# Candunio.net
KiCad netlist of a schematic drawn in Altium Designer
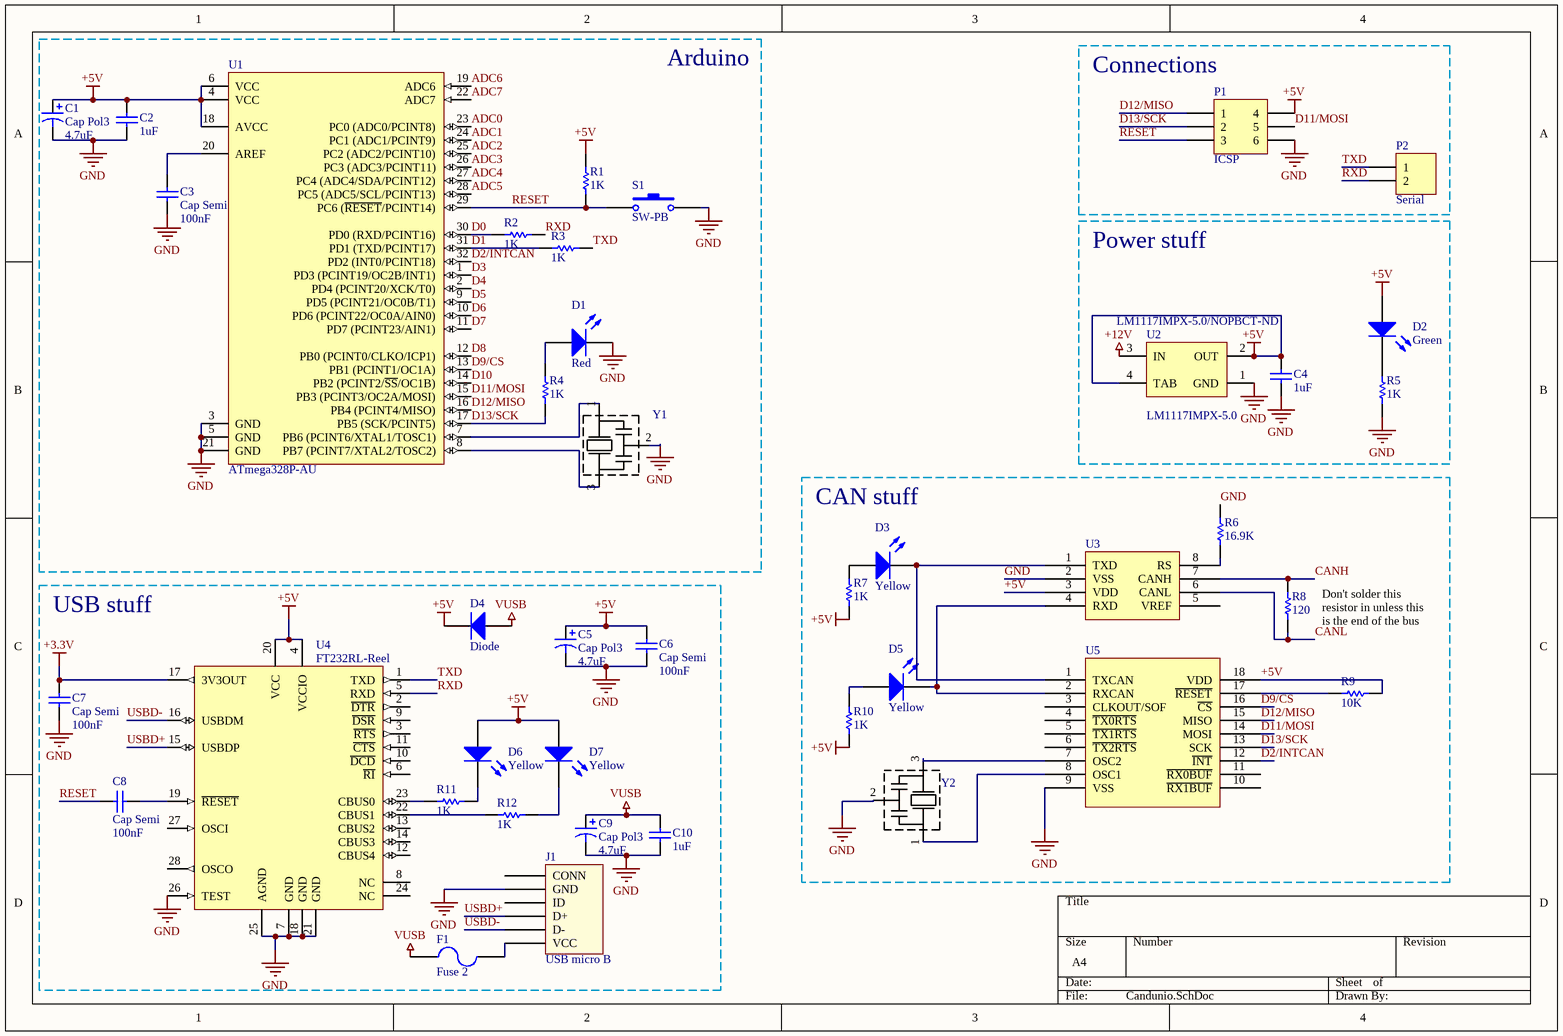
[diagram p0: Candunio.SchDoc]

(export (version "E")
  (design (tool "Eeschema 10.0.6"))
  (components
    (comp (ref "C1")
      (value "Cap Pol3")
      (footprint "C1206")
      (description "Polarized Capacitor (Surface Mount)")
      (fields
        (field (name "ALTIUM_VALUE") "4.7uF")
        (field (name "MANUFACTURER") "Kyocera AVX")
        (field (name "MANUFACTURER PART NUMBER") "12063C475KAT2A")
        (field (name "PUBLISHER") "Altium Limited")
      )
      (libsource (lib "Miscellaneous Devices") (part "Cap Pol3"))
    )
    (comp (ref "C2")
      (value "1uF")
      (footprint "C1206")
      (description "Capacitor (Semiconductor SIM Model)")
      (fields
        (field (name "MANUFACTURER") "Murata")
        (field (name "MANUFACTURER PART NUMBER") "GRM31MR71H105KA88L")
        (field (name "PUBLISHER") "Altium Limited")
      )
      (libsource (lib "Miscellaneous Devices") (part "Cap Semi"))
    )
    (comp (ref "C3")
      (value "Cap Semi")
      (footprint "C1206")
      (description "Capacitor (Semiconductor SIM Model)")
      (fields
        (field (name "ALTIUM_VALUE") "100nF")
        (field (name "MANUFACTURER") "Yageo")
        (field (name "MANUFACTURER PART NUMBER") "CC1206KKX7R0BB104")
        (field (name "PUBLISHER") "Altium Limited")
      )
      (libsource (lib "Miscellaneous Devices") (part "Cap Semi"))
    )
    (comp (ref "C4")
      (value "1uF")
      (footprint "C1206")
      (description "Capacitor (Semiconductor SIM Model)")
      (fields
        (field (name "MANUFACTURER") "Murata")
        (field (name "MANUFACTURER PART NUMBER") "GRM31MR71H105KA88L")
        (field (name "PUBLISHER") "Altium Limited")
      )
      (libsource (lib "Miscellaneous Devices") (part "Cap Semi"))
    )
    (comp (ref "C5")
      (value "Cap Pol3")
      (footprint "C1206")
      (description "Polarized Capacitor (Surface Mount)")
      (fields
        (field (name "ALTIUM_VALUE") "4.7uF")
        (field (name "MANUFACTURER") "Kyocera AVX")
        (field (name "MANUFACTURER PART NUMBER") "12063C475KAT2A")
        (field (name "PUBLISHER") "Altium Limited")
      )
      (libsource (lib "Miscellaneous Devices") (part "Cap Pol3"))
    )
    (comp (ref "C6")
      (value "Cap Semi")
      (footprint "C1206")
      (description "Capacitor (Semiconductor SIM Model)")
      (fields
        (field (name "ALTIUM_VALUE") "100nF")
        (field (name "MANUFACTURER") "Yageo")
        (field (name "MANUFACTURER PART NUMBER") "CC1206KKX7R0BB104")
        (field (name "PUBLISHER") "Altium Limited")
      )
      (libsource (lib "Miscellaneous Devices") (part "Cap Semi"))
    )
    (comp (ref "C7")
      (value "Cap Semi")
      (footprint "C1206")
      (description "Capacitor (Semiconductor SIM Model)")
      (fields
        (field (name "ALTIUM_VALUE") "100nF")
        (field (name "MANUFACTURER") "Yageo")
        (field (name "MANUFACTURER PART NUMBER") "CC1206KKX7R0BB104")
        (field (name "PUBLISHER") "Altium Limited")
      )
      (libsource (lib "Miscellaneous Devices") (part "Cap Semi"))
    )
    (comp (ref "C8")
      (value "Cap Semi")
      (footprint "C1206")
      (description "Capacitor (Semiconductor SIM Model)")
      (fields
        (field (name "ALTIUM_VALUE") "100nF")
        (field (name "MANUFACTURER") "Yageo")
        (field (name "MANUFACTURER PART NUMBER") "CC1206KKX7R0BB104")
        (field (name "PUBLISHER") "Altium Limited")
      )
      (libsource (lib "Miscellaneous Devices") (part "Cap Semi"))
    )
    (comp (ref "C9")
      (value "Cap Pol3")
      (footprint "C1206")
      (description "Polarized Capacitor (Surface Mount)")
      (fields
        (field (name "ALTIUM_VALUE") "4.7uF")
        (field (name "MANUFACTURER") "Kyocera AVX")
        (field (name "MANUFACTURER PART NUMBER") "12063C475KAT2A")
        (field (name "PUBLISHER") "Altium Limited")
      )
      (libsource (lib "Miscellaneous Devices") (part "Cap Pol3"))
    )
    (comp (ref "C10")
      (value "1uF")
      (footprint "C1206")
      (description "Capacitor (Semiconductor SIM Model)")
      (fields
        (field (name "MANUFACTURER") "Murata")
        (field (name "MANUFACTURER PART NUMBER") "GRM31MR71H105KA88L")
        (field (name "PUBLISHER") "Altium Limited")
      )
      (libsource (lib "Miscellaneous Devices") (part "Cap Semi"))
    )
    (comp (ref "D1")
      (value "Red")
      (footprint "3.2X1.6X1.1")
      (description "Typical RED, GREEN, YELLOW, AMBER GaAs LED")
      (fields
        (field (name "MANUFACTURER") "Broadcom Avago")
        (field (name "MANUFACTURER PART NUMBER") "HSMY-C150")
        (field (name "PUBLISHER") "Altium Limited")
      )
      (libsource (lib "Miscellaneous Devices") (part "LED2"))
    )
    (comp (ref "D2")
      (value "Green")
      (footprint "3.2X1.6X1.1")
      (description "Typical RED, GREEN, YELLOW, AMBER GaAs LED")
      (fields
        (field (name "MANUFACTURER") "Broadcom Avago")
        (field (name "MANUFACTURER PART NUMBER") "HSMG-C150")
        (field (name "PUBLISHER") "Altium Limited")
      )
      (libsource (lib "Miscellaneous Devices") (part "LED2"))
    )
    (comp (ref "D3")
      (value "Yellow")
      (footprint "3.2X1.6X1.1")
      (description "Typical RED, GREEN, YELLOW, AMBER GaAs LED")
      (fields
        (field (name "MANUFACTURER") "Broadcom Avago")
        (field (name "MANUFACTURER PART NUMBER") "HSMY-C150")
        (field (name "PUBLISHER") "Altium Limited")
      )
      (libsource (lib "Miscellaneous Devices") (part "LED2"))
    )
    (comp (ref "D4")
      (value "Diode")
      (footprint "SMC")
      (description "Default Diode")
      (fields (field (name "PUBLISHER") "Altium Limited"))
      (libsource (lib "Miscellaneous Devices") (part "Diode"))
    )
    (comp (ref "D5")
      (value "Yellow")
      (footprint "3.2X1.6X1.1")
      (description "Typical RED, GREEN, YELLOW, AMBER GaAs LED")
      (fields
        (field (name "MANUFACTURER") "Broadcom Avago")
        (field (name "MANUFACTURER PART NUMBER") "HSMY-C150")
        (field (name "PUBLISHER") "Altium Limited")
      )
      (libsource (lib "Miscellaneous Devices") (part "LED2"))
    )
    (comp (ref "D6")
      (value "Yellow")
      (footprint "3.2X1.6X1.1")
      (description "Typical RED, GREEN, YELLOW, AMBER GaAs LED")
      (fields
        (field (name "MANUFACTURER") "Broadcom Avago")
        (field (name "MANUFACTURER PART NUMBER") "HSMY-C150")
        (field (name "PUBLISHER") "Altium Limited")
      )
      (libsource (lib "Miscellaneous Devices") (part "LED2"))
    )
    (comp (ref "D7")
      (value "Yellow")
      (footprint "3.2X1.6X1.1")
      (description "Typical RED, GREEN, YELLOW, AMBER GaAs LED")
      (fields
        (field (name "MANUFACTURER") "Broadcom Avago")
        (field (name "MANUFACTURER PART NUMBER") "HSMY-C150")
        (field (name "PUBLISHER") "Altium Limited")
      )
      (libsource (lib "Miscellaneous Devices") (part "LED2"))
    )
    (comp (ref "F1")
      (value "Fuse 2")
      (footprint "1812")
      (description "Fuse")
      (fields
        (field (name "PART NUMBER") "MF-MSMF050-2")
        (field (name "MANUFACTURER") "Bourns")
        (field (name "PUBLISHER") "Altium Limited")
      )
      (libsource (lib "Miscellaneous Devices") (part "Fuse 2"))
    )
    (comp (ref "J1")
      (value "USB micro B")
      (footprint "1050170001")
      (description "CONN SM TH USB MICRO MODIFIED FOR DRILL")
      (fields (field (name "PART NUMBER") "WM1399CT-ND"))
      (libsource (lib "electronpowered") (part "1050170001"))
    )
    (comp (ref "P1")
      (value "ICSP")
      (footprint "HDR2X3_CEN")
      (description "Header, 3-Pin, Dual row")
      (fields (field (name "PUBLISHER") "Altium Limited"))
      (libsource (lib "Miscellaneous Connectors") (part "Header 3X2A"))
    )
    (comp (ref "P2")
      (value "Serial")
      (footprint "HDR1X2")
      (description "Header, 2-Pin")
      (fields (field (name "PUBLISHER") "Altium Limited"))
      (libsource (lib "Miscellaneous Connectors") (part "Header 2"))
    )
    (comp (ref "R1")
      (value "1K")
      (footprint "C1206")
      (description "Resistor")
      (fields
        (field (name "MANUFACTURER") "Stackpole Electronics")
        (field (name "MANUFACTURER PART NUMBER") "RNCP1206FTD1K00")
      )
      (libsource (lib "Miscellaneous Devices") (part "Res1"))
    )
    (comp (ref "R2")
      (value "1K")
      (footprint "C1206")
      (description "Resistor")
      (fields
        (field (name "MANUFACTURER") "Stackpole Electronics")
        (field (name "MANUFACTURER PART NUMBER") "RNCP1206FTD1K00")
      )
      (libsource (lib "Miscellaneous Devices") (part "Res1"))
    )
    (comp (ref "R3")
      (value "1K")
      (footprint "C1206")
      (description "Resistor")
      (fields
        (field (name "MANUFACTURER") "Stackpole Electronics")
        (field (name "MANUFACTURER PART NUMBER") "RNCP1206FTD1K00")
      )
      (libsource (lib "Miscellaneous Devices") (part "Res1"))
    )
    (comp (ref "R4")
      (value "1K")
      (footprint "C1206")
      (description "Resistor")
      (fields
        (field (name "MANUFACTURER") "Stackpole Electronics")
        (field (name "MANUFACTURER PART NUMBER") "RNCP1206FTD1K00")
      )
      (libsource (lib "Miscellaneous Devices") (part "Res1"))
    )
    (comp (ref "R5")
      (value "1K")
      (footprint "C1206")
      (description "Resistor")
      (fields
        (field (name "MANUFACTURER") "Stackpole Electronics")
        (field (name "MANUFACTURER PART NUMBER") "RNCP1206FTD1K00")
      )
      (libsource (lib "Miscellaneous Devices") (part "Res1"))
    )
    (comp (ref "R6")
      (value "16.9K")
      (footprint "C1206")
      (description "Resistor")
      (fields
        (field (name "MANUFACTURER") "TE Connectivity Holsworthy")
        (field (name "MANUFACTURER PART NUMBER") "CRGH1206F16K9")
      )
      (libsource (lib "Miscellaneous Devices") (part "Res1"))
    )
    (comp (ref "R7")
      (value "1K")
      (footprint "C1206")
      (description "Resistor")
      (fields
        (field (name "MANUFACTURER") "Stackpole Electronics")
        (field (name "MANUFACTURER PART NUMBER") "RNCP1206FTD1K00")
      )
      (libsource (lib "Miscellaneous Devices") (part "Res1"))
    )
    (comp (ref "R8")
      (value "120")
      (footprint "C1206")
      (description "Resistor")
      (fields
        (field (name "MANUFACTURER") "Vishay")
        (field (name "MANUFACTURER PART NUMBER") "CRCW1206120RFKEAHP")
      )
      (libsource (lib "Miscellaneous Devices") (part "Res1"))
    )
    (comp (ref "R9")
      (value "10K")
      (footprint "C1206")
      (description "Resistor")
      (fields
        (field (name "MANUFACTURER") "Stackpole Electronics")
        (field (name "MANUFACTURER PART NUMBER") "RNCP1206FTD10K0")
      )
      (libsource (lib "Miscellaneous Devices") (part "Res1"))
    )
    (comp (ref "R10")
      (value "1K")
      (footprint "C1206")
      (description "Resistor")
      (fields
        (field (name "MANUFACTURER") "Stackpole Electronics")
        (field (name "MANUFACTURER PART NUMBER") "RNCP1206FTD1K00")
      )
      (libsource (lib "Miscellaneous Devices") (part "Res1"))
    )
    (comp (ref "R11")
      (value "1K")
      (footprint "C1206")
      (description "Resistor")
      (fields
        (field (name "MANUFACTURER") "Stackpole Electronics")
        (field (name "MANUFACTURER PART NUMBER") "RNCP1206FTD1K00")
      )
      (libsource (lib "Miscellaneous Devices") (part "Res1"))
    )
    (comp (ref "R12")
      (value "1K")
      (footprint "C1206")
      (description "Resistor")
      (fields
        (field (name "MANUFACTURER") "Stackpole Electronics")
        (field (name "MANUFACTURER PART NUMBER") "RNCP1206FTD1K00")
      )
      (libsource (lib "Miscellaneous Devices") (part "Res1"))
    )
    (comp (ref "S1")
      (value "SW-PB")
      (footprint "C1206")
      (description "Switch")
      (fields
        (field (name "MANUFACTURER") "ITT C&K")
        (field (name "MANUFACTURER PART NUMBER") "KXT331LHS")
        (field (name "PUBLISHER") "Altium Limited")
      )
      (libsource (lib "Miscellaneous Devices") (part "SW-PB"))
    )
    (comp (ref "U1")
      (value "ATmega328P-AU")
      (footprint "32A_N")
      (fields (field (name "PUBLISHER") "Altium Limited"))
      (libsource (lib "Atmel Microcontroller 8-Bit megaAVR") (part "ATmega328P-AU"))
    )
    (comp (ref "U2")
      (value "LM1117IMPX-5.0")
      (footprint "MP04A_N")
      (description "800mA Low-Dropout Linear Regulator, 4-pin SOT-223")
      (fields
        (field (name "PARTNUMBER") "LM1117IMPX-5.0/NOPBCT-ND")
        (field (name "MANUFACTURER") "National Semiconductor")
        (field (name "SUPPLIER PART NUMBER") "LM1117IMPX-5.0/NOPBCT-ND")
        (field (name "PUBLISHER") "Altium Limited")
      )
      (libsource (lib "NSC LDO") (part "LM1117IMPX-5.0"))
    )
    (comp (ref "U3")
      (value "MCP2551-E/SN")
      (footprint "SOIC127P600X175-8M")
      (description "SOIC")
      (libsource (lib "AMSComponents") (part "MCP2551-E/SN"))
    )
    (comp (ref "U4")
      (value "FT232RL-Reel")
      (footprint "SSOP-28_N")
      (description "USB UART Asynchronous Serial Data Transfer Chip, SSOP-28, Tape and Reel")
      (fields
        (field (name "MANUFACTURER") "FTDI")
        (field (name "MANUFACTURER PART NUMBER") "FT232RL-REEL")
        (field (name "PUBLISHER") "Altium Limited")
      )
      (libsource (lib "FTDI Communication UART") (part "FT232RL-Reel"))
    )
    (comp (ref "U5")
      (value "MCP2515-E/ST")
      (footprint "SOIC127P1030X265-18M")
      (description "SOIC")
      (libsource (lib "AMSComponents") (part "MCP2515-E/ST"))
    )
    (comp (ref "Y1")
      (value "CSTCE16M0V53-R0")
      (footprint "CSTCE16M0V53-R0")
      (fields
        (field (name "MANUFACTURER") "Murata")
        (field (name "MANUFACTURER PART NUMBER") "CSTCE16M0V53C-R0")
        (field (name "TOLERANCE") "0.5%")
      )
      (libsource (lib "AMSComponents") (part "CSTCE16M0V53-R0"))
    )
    (comp (ref "Y2")
      (value "CSTCE16M0V53-R0")
      (footprint "CSTCE16M0V53-R0")
      (fields
        (field (name "MANUFACTURER") "Murata")
        (field (name "MANUFACTURER PART NUMBER") "CSTCE16M0V53C-R0")
        (field (name "TOLERANCE") "0.5%")
      )
      (libsource (lib "AMSComponents") (part "CSTCE16M0V53-R0"))
    )
  )
  (nets
    (net (code "1") (name "+3.3V") (class "Default")
      (node (ref "C7") (pin "1") (pinfunction "1_1") (pintype "passive"))
      (node (ref "U4") (pin "17") (pinfunction "3V3OUT_17") (pintype "output"))
    )
    (net (code "2") (name "+5V") (class "Default")
      (node (ref "C1") (pin "1") (pinfunction "1_1") (pintype "passive"))
      (node (ref "C2") (pin "1") (pinfunction "1_1") (pintype "passive"))
      (node (ref "C4") (pin "1") (pinfunction "1_1") (pintype "passive"))
      (node (ref "C5") (pin "1") (pinfunction "1_1") (pintype "passive"))
      (node (ref "C6") (pin "1") (pinfunction "1_1") (pintype "passive"))
      (node (ref "D2") (pin "1") (pinfunction "A_1") (pintype "passive"))
      (node (ref "D4") (pin "2") (pinfunction "K_2") (pintype "passive"))
      (node (ref "D6") (pin "1") (pinfunction "A_1") (pintype "passive"))
      (node (ref "D7") (pin "1") (pinfunction "A_1") (pintype "passive"))
      (node (ref "P1") (pin "4") (pinfunction "4_4") (pintype "passive"))
      (node (ref "R1") (pin "1") (pinfunction "1_1") (pintype "passive"))
      (node (ref "R10") (pin "2") (pinfunction "2_2") (pintype "passive"))
      (node (ref "R7") (pin "1") (pinfunction "1_1") (pintype "passive"))
      (node (ref "R9") (pin "2") (pinfunction "2_2") (pintype "passive"))
      (node (ref "U1") (pin "18") (pinfunction "AVCC_18") (pintype "power_in"))
      (node (ref "U1") (pin "4") (pinfunction "VCC_4") (pintype "power_in"))
      (node (ref "U1") (pin "6") (pinfunction "VCC_6") (pintype "power_in"))
      (node (ref "U2") (pin "2") (pinfunction "OUT_2") (pintype "power_in"))
      (node (ref "U2") (pin "4") (pinfunction "TAB_4") (pintype "power_in"))
      (node (ref "U3") (pin "3") (pinfunction "VDD_3") (pintype "passive"))
      (node (ref "U4") (pin "20") (pinfunction "VCC_20") (pintype "power_in"))
      (node (ref "U4") (pin "4") (pinfunction "VCCIO_4") (pintype "power_in"))
      (node (ref "U5") (pin "18") (pinfunction "VDD_18") (pintype "passive"))
    )
    (net (code "3") (name "+12V") (class "Default")
      (node (ref "U2") (pin "3") (pinfunction "IN_3") (pintype "power_in"))
    )
    (net (code "4") (name "/ADC0") (class "Default")
      (node (ref "U1") (pin "23") (pinfunction "PC0_(ADC0/PCINT8)_23") (pintype "bidirectional"))
    )
    (net (code "5") (name "/ADC1") (class "Default")
      (node (ref "U1") (pin "24") (pinfunction "PC1_(ADC1/PCINT9)_24") (pintype "bidirectional"))
    )
    (net (code "6") (name "/ADC2") (class "Default")
      (node (ref "U1") (pin "25") (pinfunction "PC2_(ADC2/PCINT10)_25") (pintype "bidirectional"))
    )
    (net (code "7") (name "/ADC3") (class "Default")
      (node (ref "U1") (pin "26") (pinfunction "PC3_(ADC3/PCINT11)_26") (pintype "bidirectional"))
    )
    (net (code "8") (name "/ADC4") (class "Default")
      (node (ref "U1") (pin "27") (pinfunction "PC4_(ADC4/SDA/PCINT12)_27") (pintype "bidirectional"))
    )
    (net (code "9") (name "/ADC5") (class "Default")
      (node (ref "U1") (pin "28") (pinfunction "PC5_(ADC5/SCL/PCINT13)_28") (pintype "bidirectional"))
    )
    (net (code "10") (name "/ADC6") (class "Default")
      (node (ref "U1") (pin "19") (pinfunction "ADC6_19") (pintype "input"))
    )
    (net (code "11") (name "/ADC7") (class "Default")
      (node (ref "U1") (pin "22") (pinfunction "ADC7_22") (pintype "input"))
    )
    (net (code "12") (name "/CANH") (class "Default")
      (node (ref "R8") (pin "1") (pinfunction "1_1") (pintype "passive"))
      (node (ref "U3") (pin "7") (pinfunction "CANH_7") (pintype "passive"))
    )
    (net (code "13") (name "/CANL") (class "Default")
      (node (ref "R8") (pin "2") (pinfunction "2_2") (pintype "passive"))
      (node (ref "U3") (pin "6") (pinfunction "CANL_6") (pintype "passive"))
    )
    (net (code "14") (name "/D0") (class "Default")
      (node (ref "R2") (pin "1") (pinfunction "1_1") (pintype "passive"))
      (node (ref "U1") (pin "30") (pinfunction "PD0_(RXD/PCINT16)_30") (pintype "bidirectional"))
    )
    (net (code "15") (name "/D1") (class "Default")
      (node (ref "R3") (pin "1") (pinfunction "1_1") (pintype "passive"))
      (node (ref "U1") (pin "31") (pinfunction "PD1_(TXD/PCINT17)_31") (pintype "bidirectional"))
    )
    (net (code "16") (name "/D2{slash}INTCAN") (class "Default")
      (node (ref "U1") (pin "32") (pinfunction "PD2_(INT0/PCINT18)_32") (pintype "bidirectional"))
      (node (ref "U5") (pin "12") (pinfunction "~{INT}_12") (pintype "passive"))
    )
    (net (code "17") (name "/D3") (class "Default")
      (node (ref "U1") (pin "1") (pinfunction "PD3_(PCINT19/OC2B/INT1)_1") (pintype "bidirectional"))
    )
    (net (code "18") (name "/D4") (class "Default")
      (node (ref "U1") (pin "2") (pinfunction "PD4_(PCINT20/XCK/T0)_2") (pintype "bidirectional"))
    )
    (net (code "19") (name "/D5") (class "Default")
      (node (ref "U1") (pin "9") (pinfunction "PD5_(PCINT21/OC0B/T1)_9") (pintype "bidirectional"))
    )
    (net (code "20") (name "/D6") (class "Default")
      (node (ref "U1") (pin "10") (pinfunction "PD6_(PCINT22/OC0A/AIN0)_10") (pintype "bidirectional"))
    )
    (net (code "21") (name "/D7") (class "Default")
      (node (ref "U1") (pin "11") (pinfunction "PD7_(PCINT23/AIN1)_11") (pintype "bidirectional"))
    )
    (net (code "22") (name "/D8") (class "Default")
      (node (ref "U1") (pin "12") (pinfunction "PB0_(PCINT0/CLKO/ICP1)_12") (pintype "bidirectional"))
    )
    (net (code "23") (name "/D9{slash}CS") (class "Default")
      (node (ref "U1") (pin "13") (pinfunction "PB1_(PCINT1/OC1A)_13") (pintype "bidirectional"))
      (node (ref "U5") (pin "16") (pinfunction "~{CS}_16") (pintype "passive"))
    )
    (net (code "24") (name "/D10") (class "Default")
      (node (ref "U1") (pin "14") (pinfunction "PB2_(PCINT2/~{SS}/OC1B)_14") (pintype "bidirectional"))
    )
    (net (code "25") (name "/D11{slash}MOSI") (class "Default")
      (node (ref "P1") (pin "5") (pinfunction "5_5") (pintype "passive"))
      (node (ref "U1") (pin "15") (pinfunction "PB3_(PCINT3/OC2A/MOSI)_15") (pintype "bidirectional"))
      (node (ref "U5") (pin "14") (pinfunction "MOSI_14") (pintype "passive"))
    )
    (net (code "26") (name "/D12{slash}MISO") (class "Default")
      (node (ref "P1") (pin "1") (pinfunction "1_1") (pintype "passive"))
      (node (ref "U1") (pin "16") (pinfunction "PB4_(PCINT4/MISO)_16") (pintype "bidirectional"))
      (node (ref "U5") (pin "15") (pinfunction "MISO_15") (pintype "passive"))
    )
    (net (code "27") (name "/D13{slash}SCK") (class "Default")
      (node (ref "P1") (pin "2") (pinfunction "2_2") (pintype "passive"))
      (node (ref "R4") (pin "2") (pinfunction "2_2") (pintype "passive"))
      (node (ref "U1") (pin "17") (pinfunction "PB5_(SCK/PCINT5)_17") (pintype "bidirectional"))
      (node (ref "U5") (pin "13") (pinfunction "SCK_13") (pintype "passive"))
    )
    (net (code "28") (name "/RESET") (class "Default")
      (node (ref "C8") (pin "1") (pinfunction "1_1") (pintype "passive"))
      (node (ref "P1") (pin "3") (pinfunction "3_3") (pintype "passive"))
      (node (ref "R1") (pin "2") (pinfunction "2_2") (pintype "passive"))
      (node (ref "S1") (pin "1") (pinfunction "1_1") (pintype "passive"))
      (node (ref "U1") (pin "29") (pinfunction "PC6_(~{RESET}/PCINT14)_29") (pintype "bidirectional"))
    )
    (net (code "29") (name "/RXD") (class "Default")
      (node (ref "P2") (pin "2") (pinfunction "2_2") (pintype "passive"))
      (node (ref "R2") (pin "2") (pinfunction "2_2") (pintype "passive"))
      (node (ref "U4") (pin "5") (pinfunction "RXD_5") (pintype "input"))
    )
    (net (code "30") (name "/TXD") (class "Default")
      (node (ref "P2") (pin "1") (pinfunction "1_1") (pintype "passive"))
      (node (ref "R3") (pin "2") (pinfunction "2_2") (pintype "passive"))
      (node (ref "U4") (pin "1") (pinfunction "TXD_1") (pintype "output"))
    )
    (net (code "31") (name "/USBD+") (class "Default")
      (node (ref "J1") (pin "3") (pinfunction "D+_3") (pintype "passive"))
      (node (ref "U4") (pin "15") (pinfunction "USBDP_15") (pintype "bidirectional"))
    )
    (net (code "32") (name "/USBD-") (class "Default")
      (node (ref "J1") (pin "2") (pinfunction "D-_2") (pintype "passive"))
      (node (ref "U4") (pin "16") (pinfunction "USBDM_16") (pintype "bidirectional"))
    )
    (net (code "33") (name "GND") (class "Default")
      (node (ref "C1") (pin "2") (pinfunction "2_2") (pintype "passive"))
      (node (ref "C10") (pin "2") (pinfunction "2_2") (pintype "passive"))
      (node (ref "C2") (pin "2") (pinfunction "2_2") (pintype "passive"))
      (node (ref "C3") (pin "2") (pinfunction "2_2") (pintype "passive"))
      (node (ref "C4") (pin "2") (pinfunction "2_2") (pintype "passive"))
      (node (ref "C5") (pin "2") (pinfunction "2_2") (pintype "passive"))
      (node (ref "C6") (pin "2") (pinfunction "2_2") (pintype "passive"))
      (node (ref "C7") (pin "2") (pinfunction "2_2") (pintype "passive"))
      (node (ref "C9") (pin "2") (pinfunction "2_2") (pintype "passive"))
      (node (ref "D1") (pin "2") (pinfunction "K_2") (pintype "passive"))
      (node (ref "J1") (pin "5") (pinfunction "GND_5") (pintype "passive"))
      (node (ref "P1") (pin "6") (pinfunction "6_6") (pintype "passive"))
      (node (ref "R5") (pin "2") (pinfunction "2_2") (pintype "passive"))
      (node (ref "R6") (pin "1") (pinfunction "1_1") (pintype "passive"))
      (node (ref "S1") (pin "2") (pinfunction "2_2") (pintype "passive"))
      (node (ref "U1") (pin "21") (pinfunction "GND_21") (pintype "power_in"))
      (node (ref "U1") (pin "3") (pinfunction "GND_3") (pintype "power_in"))
      (node (ref "U1") (pin "5") (pinfunction "GND_5") (pintype "power_in"))
      (node (ref "U2") (pin "1") (pinfunction "GND_1") (pintype "power_in"))
      (node (ref "U3") (pin "2") (pinfunction "VSS_2") (pintype "passive"))
      (node (ref "U4") (pin "18") (pinfunction "GND_18") (pintype "power_in"))
      (node (ref "U4") (pin "21") (pinfunction "GND_21") (pintype "power_in"))
      (node (ref "U4") (pin "25") (pinfunction "AGND_25") (pintype "power_in"))
      (node (ref "U4") (pin "26") (pinfunction "TEST_26") (pintype "input"))
      (node (ref "U4") (pin "7") (pinfunction "GND_7") (pintype "power_in"))
      (node (ref "U5") (pin "9") (pinfunction "VSS_9") (pintype "passive"))
      (node (ref "Y1") (pin "2") (pinfunction "2_2") (pintype "passive"))
      (node (ref "Y2") (pin "2") (pinfunction "2_2") (pintype "passive"))
    )
    (net (code "34") (name "Net-(D1-A)") (class "Default")
      (node (ref "D1") (pin "1") (pinfunction "A_1") (pintype "passive"))
      (node (ref "R4") (pin "1") (pinfunction "1_1") (pintype "passive"))
    )
    (net (code "35") (name "Net-(D2-K)") (class "Default")
      (node (ref "D2") (pin "2") (pinfunction "K_2") (pintype "passive"))
      (node (ref "R5") (pin "1") (pinfunction "1_1") (pintype "passive"))
    )
    (net (code "36") (name "Net-(D3-A)") (class "Default")
      (node (ref "D3") (pin "1") (pinfunction "A_1") (pintype "passive"))
      (node (ref "R7") (pin "2") (pinfunction "2_2") (pintype "passive"))
    )
    (net (code "37") (name "Net-(D3-K)") (class "Default")
      (node (ref "D3") (pin "2") (pinfunction "K_2") (pintype "passive"))
      (node (ref "U3") (pin "1") (pinfunction "TXD_1") (pintype "passive"))
      (node (ref "U5") (pin "1") (pinfunction "TXCAN_1") (pintype "passive"))
    )
    (net (code "38") (name "Net-(D5-A)") (class "Default")
      (node (ref "D5") (pin "1") (pinfunction "A_1") (pintype "passive"))
      (node (ref "R10") (pin "1") (pinfunction "1_1") (pintype "passive"))
    )
    (net (code "39") (name "Net-(D5-K)") (class "Default")
      (node (ref "D5") (pin "2") (pinfunction "K_2") (pintype "passive"))
      (node (ref "U3") (pin "4") (pinfunction "RXD_4") (pintype "passive"))
      (node (ref "U5") (pin "2") (pinfunction "RXCAN_2") (pintype "passive"))
    )
    (net (code "40") (name "Net-(D6-K)") (class "Default")
      (node (ref "D6") (pin "2") (pinfunction "K_2") (pintype "passive"))
      (node (ref "R11") (pin "2") (pinfunction "2_2") (pintype "passive"))
    )
    (net (code "41") (name "Net-(D7-K)") (class "Default")
      (node (ref "D7") (pin "2") (pinfunction "K_2") (pintype "passive"))
      (node (ref "R12") (pin "2") (pinfunction "2_2") (pintype "passive"))
    )
    (net (code "42") (name "Net-(J1-VCC)") (class "Default")
      (node (ref "F1") (pin "2") (pinfunction "2_2") (pintype "passive"))
      (node (ref "J1") (pin "1") (pinfunction "VCC_1") (pintype "passive"))
    )
    (net (code "43") (name "Net-(U1-AREF)") (class "Default")
      (node (ref "C3") (pin "1") (pinfunction "1_1") (pintype "passive"))
      (node (ref "U1") (pin "20") (pinfunction "AREF_20") (pintype "passive"))
    )
    (net (code "44") (name "Net-(U1-PB6_(PCINT6{slash}XTAL1{slash}TOSC1))") (class "Default")
      (node (ref "U1") (pin "7") (pinfunction "PB6_(PCINT6/XTAL1/TOSC1)_7") (pintype "bidirectional"))
      (node (ref "Y1") (pin "1") (pinfunction "1_1") (pintype "passive"))
    )
    (net (code "45") (name "Net-(U1-PB7_(PCINT7{slash}XTAL2{slash}TOSC2))") (class "Default")
      (node (ref "U1") (pin "8") (pinfunction "PB7_(PCINT7/XTAL2/TOSC2)_8") (pintype "bidirectional"))
      (node (ref "Y1") (pin "3") (pinfunction "3_3") (pintype "passive"))
    )
    (net (code "46") (name "Net-(U3-RS)") (class "Default")
      (node (ref "R6") (pin "2") (pinfunction "2_2") (pintype "passive"))
      (node (ref "U3") (pin "8") (pinfunction "RS_8") (pintype "passive"))
    )
    (net (code "47") (name "Net-(U4-CBUS0)") (class "Default")
      (node (ref "R11") (pin "1") (pinfunction "1_1") (pintype "passive"))
      (node (ref "U4") (pin "23") (pinfunction "CBUS0_23") (pintype "bidirectional"))
    )
    (net (code "48") (name "Net-(U4-CBUS1)") (class "Default")
      (node (ref "R12") (pin "1") (pinfunction "1_1") (pintype "passive"))
      (node (ref "U4") (pin "22") (pinfunction "CBUS1_22") (pintype "bidirectional"))
    )
    (net (code "49") (name "Net-(U4-~{RESET})") (class "Default")
      (node (ref "C8") (pin "2") (pinfunction "2_2") (pintype "passive"))
      (node (ref "U4") (pin "19") (pinfunction "~{RESET}_19") (pintype "input"))
    )
    (net (code "50") (name "Net-(U5-OSC1)") (class "Default")
      (node (ref "U5") (pin "8") (pinfunction "OSC1_8") (pintype "passive"))
      (node (ref "Y2") (pin "1") (pinfunction "1_1") (pintype "passive"))
    )
    (net (code "51") (name "Net-(U5-OSC2)") (class "Default")
      (node (ref "U5") (pin "7") (pinfunction "OSC2_7") (pintype "passive"))
      (node (ref "Y2") (pin "3") (pinfunction "3_3") (pintype "passive"))
    )
    (net (code "52") (name "Net-(U5-~{RESET})") (class "Default")
      (node (ref "R9") (pin "1") (pinfunction "1_1") (pintype "passive"))
      (node (ref "U5") (pin "17") (pinfunction "~{RESET}_17") (pintype "passive"))
    )
    (net (code "53") (name "VUSB") (class "Default")
      (node (ref "C10") (pin "1") (pinfunction "1_1") (pintype "passive"))
      (node (ref "C9") (pin "1") (pinfunction "1_1") (pintype "passive"))
      (node (ref "D4") (pin "1") (pinfunction "A_1") (pintype "passive"))
      (node (ref "F1") (pin "1") (pinfunction "1_1") (pintype "passive"))
    )
    (net (code "54") (name "unconnected-(J1-CONN-Pad0)") (class "Default")
      (node (ref "J1") (pin "0") (pinfunction "CONN_0") (pintype "passive"))
    )
    (net (code "55") (name "unconnected-(J1-ID-Pad4)") (class "Default")
      (node (ref "J1") (pin "4") (pinfunction "ID_4") (pintype "passive"))
    )
    (net (code "56") (name "unconnected-(U3-VREF-Pad5)") (class "Default")
      (node (ref "U3") (pin "5") (pinfunction "VREF_5") (pintype "passive"))
    )
    (net (code "57") (name "unconnected-(U4-CBUS2-Pad13)") (class "Default")
      (node (ref "U4") (pin "13") (pinfunction "CBUS2_13") (pintype "bidirectional"))
    )
    (net (code "58") (name "unconnected-(U4-CBUS3-Pad14)") (class "Default")
      (node (ref "U4") (pin "14") (pinfunction "CBUS3_14") (pintype "bidirectional"))
    )
    (net (code "59") (name "unconnected-(U4-CBUS4-Pad12)") (class "Default")
      (node (ref "U4") (pin "12") (pinfunction "CBUS4_12") (pintype "bidirectional"))
    )
    (net (code "60") (name "unconnected-(U4-NC-Pad8)") (class "Default")
      (node (ref "U4") (pin "8") (pinfunction "NC_8") (pintype "passive"))
    )
    (net (code "61") (name "unconnected-(U4-NC-Pad24)") (class "Default")
      (node (ref "U4") (pin "24") (pinfunction "NC_24") (pintype "passive"))
    )
    (net (code "62") (name "unconnected-(U4-OSCI-Pad27)") (class "Default")
      (node (ref "U4") (pin "27") (pinfunction "OSCI_27") (pintype "input"))
    )
    (net (code "63") (name "unconnected-(U4-OSCO-Pad28)") (class "Default")
      (node (ref "U4") (pin "28") (pinfunction "OSCO_28") (pintype "output"))
    )
    (net (code "64") (name "unconnected-(U4-~{CTS}-Pad11)") (class "Default")
      (node (ref "U4") (pin "11") (pinfunction "~{CTS}_11") (pintype "input"))
    )
    (net (code "65") (name "unconnected-(U4-~{DCD}-Pad10)") (class "Default")
      (node (ref "U4") (pin "10") (pinfunction "~{DCD}_10") (pintype "input"))
    )
    (net (code "66") (name "unconnected-(U4-~{DSR}-Pad9)") (class "Default")
      (node (ref "U4") (pin "9") (pinfunction "~{DSR}_9") (pintype "input"))
    )
    (net (code "67") (name "unconnected-(U4-~{DTR}-Pad2)") (class "Default")
      (node (ref "U4") (pin "2") (pinfunction "~{DTR}_2") (pintype "output"))
    )
    (net (code "68") (name "unconnected-(U4-~{RI}-Pad6)") (class "Default")
      (node (ref "U4") (pin "6") (pinfunction "~{RI}_6") (pintype "input"))
    )
    (net (code "69") (name "unconnected-(U4-~{RTS}-Pad3)") (class "Default")
      (node (ref "U4") (pin "3") (pinfunction "~{RTS}_3") (pintype "output"))
    )
    (net (code "70") (name "unconnected-(U5-CLKOUT{slash}SOF-Pad3)") (class "Default")
      (node (ref "U5") (pin "3") (pinfunction "CLKOUT/SOF_3") (pintype "passive"))
    )
    (net (code "71") (name "unconnected-(U5-~{RX0BUF}-Pad11)") (class "Default")
      (node (ref "U5") (pin "11") (pinfunction "~{RX0BUF}_11") (pintype "passive"))
    )
    (net (code "72") (name "unconnected-(U5-~{RX1BUF}-Pad10)") (class "Default")
      (node (ref "U5") (pin "10") (pinfunction "~{RX1BUF}_10") (pintype "passive"))
    )
    (net (code "73") (name "unconnected-(U5-~{TX0RTS}-Pad4)") (class "Default")
      (node (ref "U5") (pin "4") (pinfunction "~{TX0RTS}_4") (pintype "passive"))
    )
    (net (code "74") (name "unconnected-(U5-~{TX1RTS}-Pad5)") (class "Default")
      (node (ref "U5") (pin "5") (pinfunction "~{TX1RTS}_5") (pintype "passive"))
    )
    (net (code "75") (name "unconnected-(U5-~{TX2RTS}-Pad6)") (class "Default")
      (node (ref "U5") (pin "6") (pinfunction "~{TX2RTS}_6") (pintype "passive"))
    )
  )
)
